# POWER.net
KiCad netlist of a schematic drawn in Altium Designer
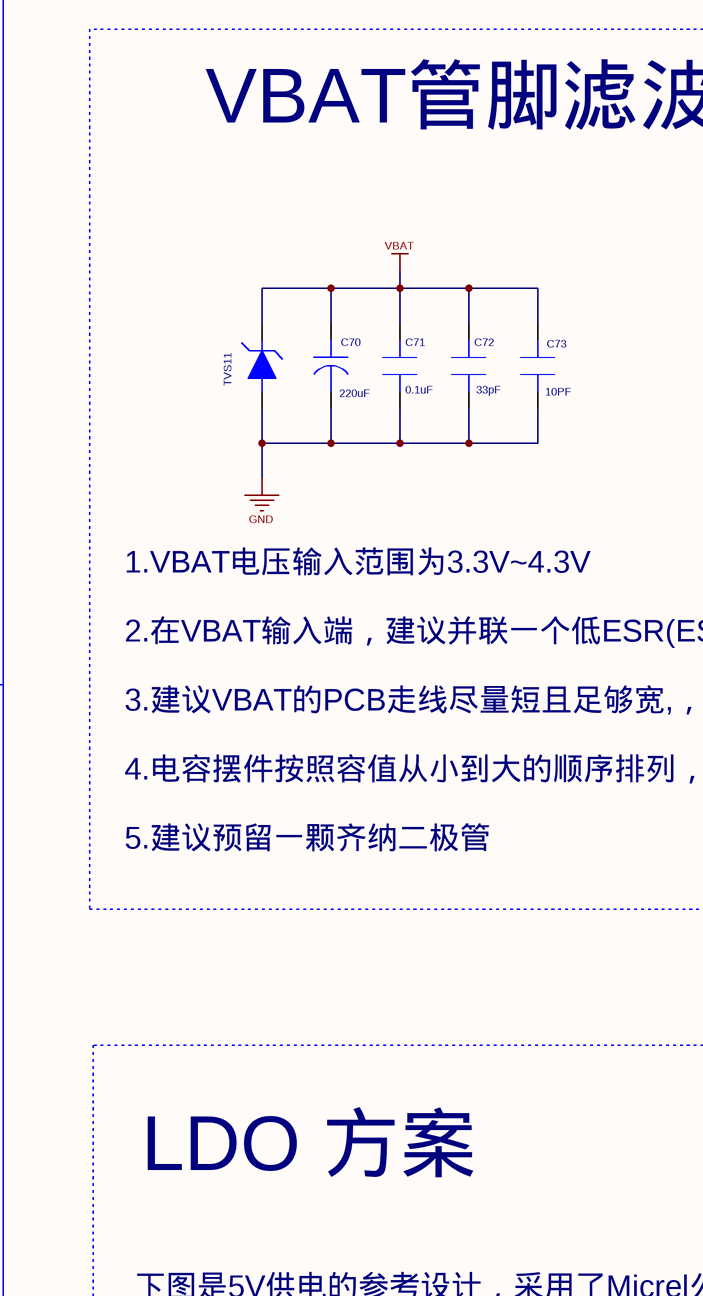
[diagram p0: POWER.SchDoc, top left]
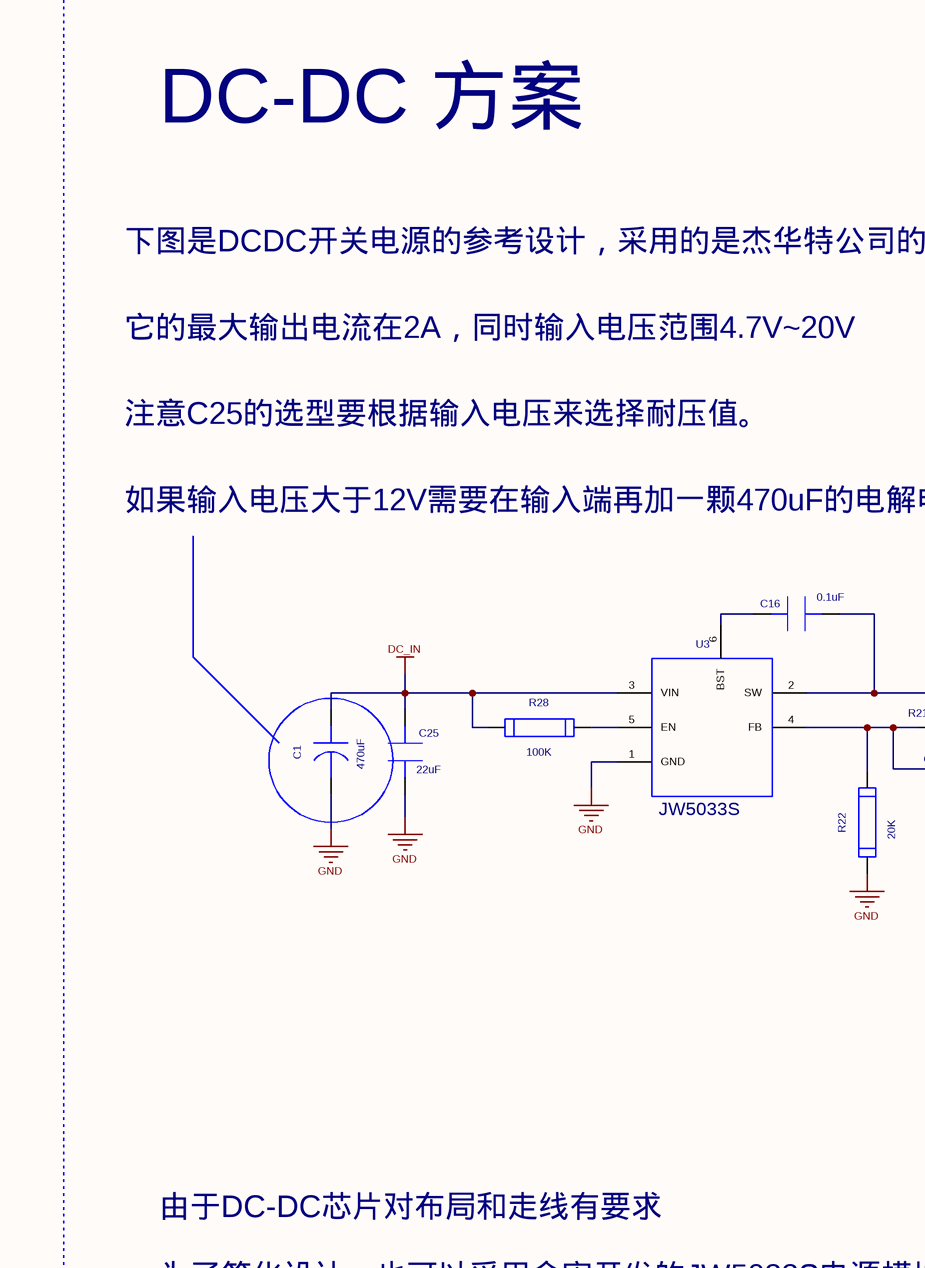
[diagram p1: POWER.SchDoc, top middle]
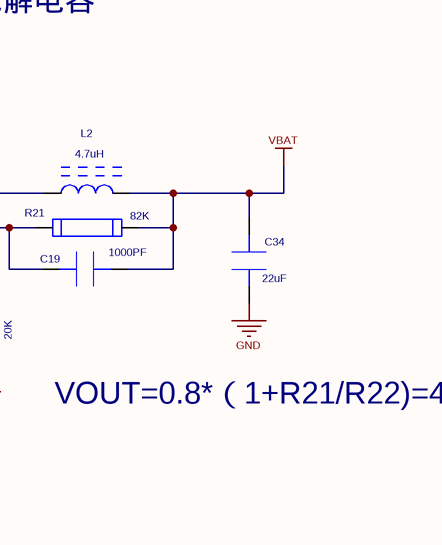
[diagram p2: POWER.SchDoc, top right]
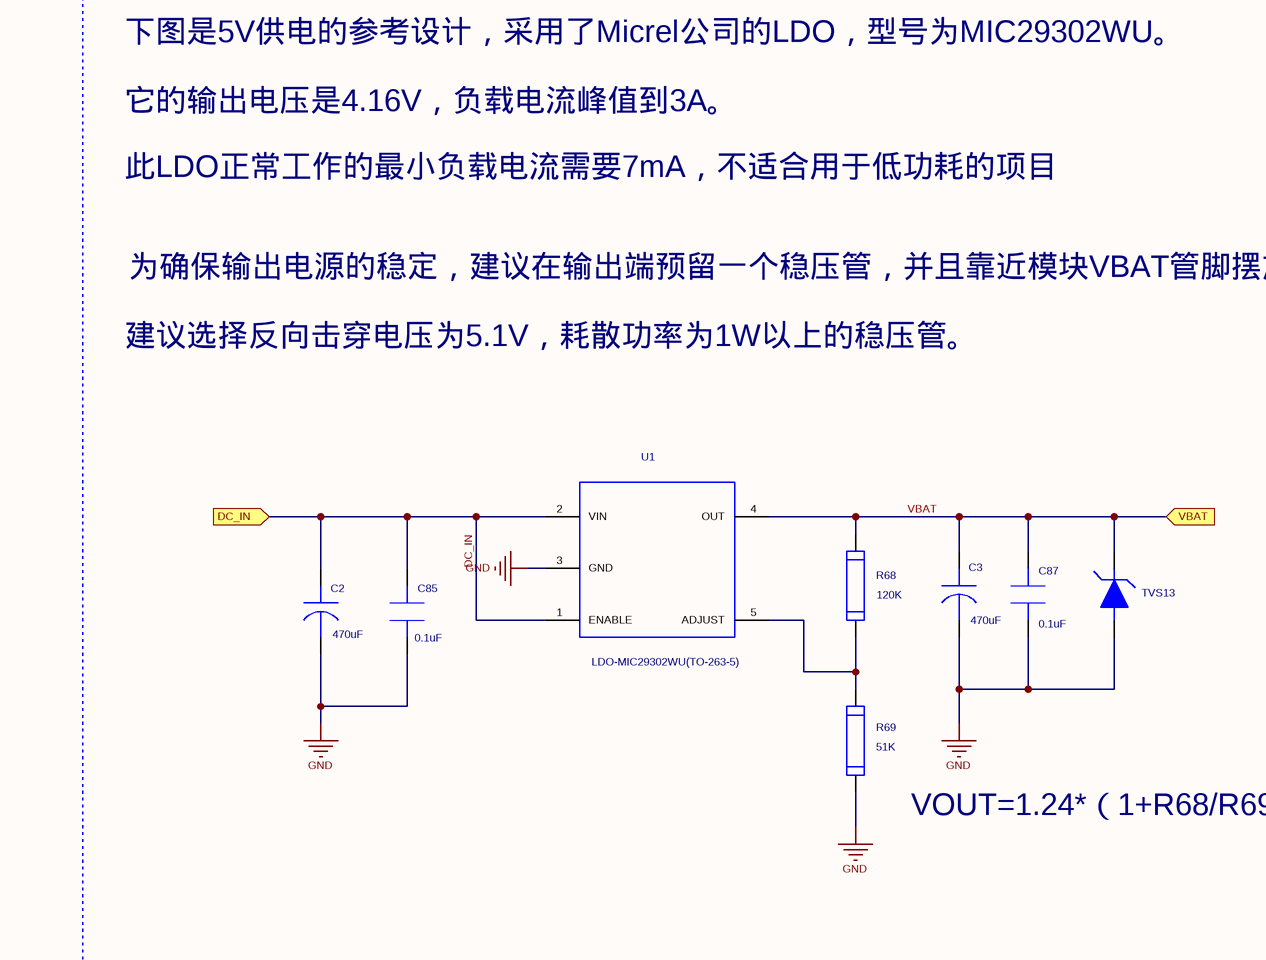
[diagram p3: POWER.SchDoc, bottom left]
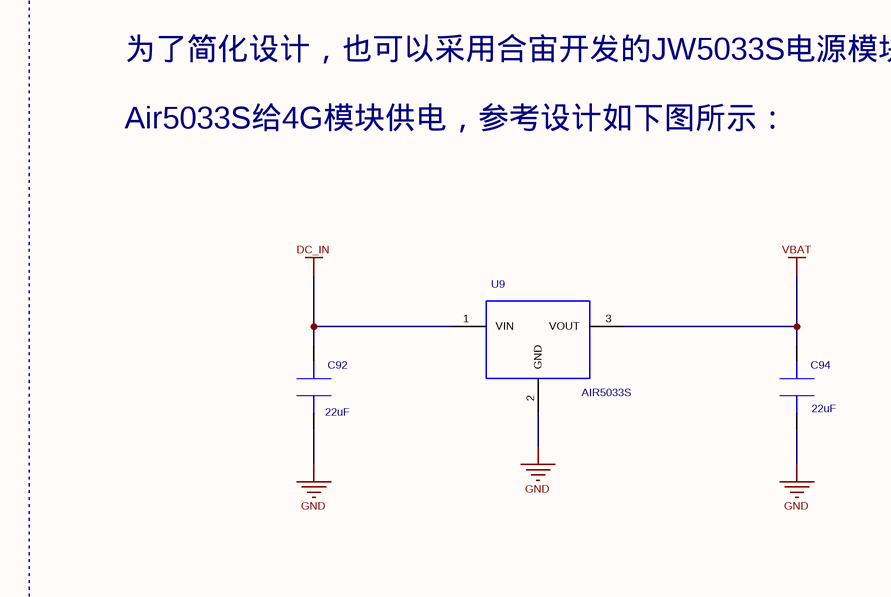
[diagram p4: POWER.SchDoc, bottom middle]
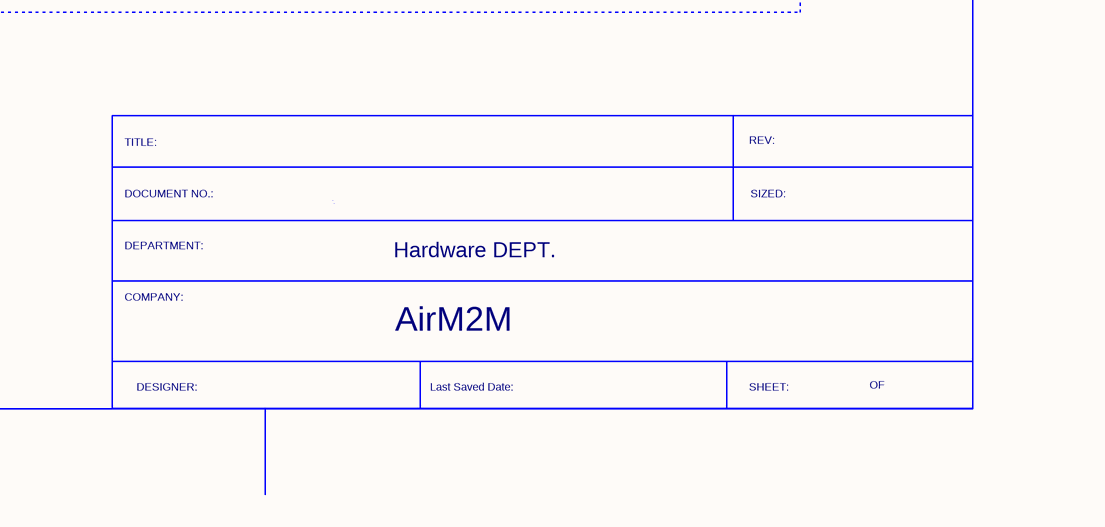
[diagram p5: POWER.SchDoc, bottom right]

(export (version "E")
  (design (tool "Eeschema 10.0.6"))
  (components
    (comp (ref "C1")
      (value "470uF")
      (footprint "CAP-PD-8MMX11.5MM-UVR1C471MPD")
      (description "铝电解电容器;470uF;+/-20%;16V;8x11.5mm;引脚间距3.5mm;ROHS")
      (fields (field (name "TOLERANCE") "+/-20%") (field (name "Comment") "CAP-AL-470UF-16V-8X11.5MM"))
      (libsource (lib "*") (part "CAP-AL-470UF-16V-8X11.5MM"))
    )
    (comp (ref "C2")
      (value "470uF")
      (footprint "CAP-PD-8MMX11.5MM-UVR1C471MPD")
      (description "铝电解电容器;470uF;+/-20%;16V;8x11.5mm;引脚间距3.5mm;ROHS")
      (fields (field (name "TOLERANCE") "+/-20%") (field (name "Comment") "CAP-AL-470UF-16V-8X11.5MM"))
      (libsource (lib "*") (part "CAP-AL-470UF-16V-8X11.5MM"))
    )
    (comp (ref "C3")
      (value "470uF")
      (footprint "CAP-PD-8MMX11.5MM-UVR1C471MPD")
      (description "铝电解电容器;470uF;+/-20%;16V;8x11.5mm;引脚间距3.5mm;ROHS")
      (fields (field (name "TOLERANCE") "+/-20%") (field (name "Comment") "CAP-AL-470UF-16V-8X11.5MM"))
      (libsource (lib "*") (part "CAP-AL-470UF-16V-8X11.5MM"))
    )
    (comp (ref "C16")
      (value "0.1uF")
      (footprint "SC0402")
      (description "CAP CER X5R/X7R;0.1uF;+/-10%;10V;0402;0.5mm;ROHS")
      (fields (field (name "TOLERANCE") "+/-10%") (field (name "Comment") "CAP-0.1UF-0402-X5R-10V"))
      (libsource (lib "*") (part "CAP-0.1UF-0402-X5R-10V"))
    )
    (comp (ref "C19")
      (value "1000PF")
      (footprint "SC0402")
      (description "CAP CER X7R;1000PF;+/-10%;50V;0402;0.5mm;ROHS")
      (fields (field (name "TOLERANCE") "+/-10%") (field (name "Comment") "CAP-1000PF-0402-X7R"))
      (libsource (lib "*") (part "CAP-1000PF-0402-X7R"))
    )
    (comp (ref "C25")
      (value "22uF")
      (footprint "SC0603")
      (description "CAP CER X5R;22uF;+/-20%;6.3V;0603;0.8mm;ROHS")
      (fields (field (name "TOLERANCE") "+/-20%") (field (name "Comment") "CAP-22UF-0603-X5R"))
      (libsource (lib "*") (part "CAP-22UF-0603-X5R"))
    )
    (comp (ref "C34")
      (value "22uF")
      (footprint "SC0603")
      (description "CAP CER X5R;4.7uF;+/-10%;6.3V;0603;0.8mm;ROHS")
      (fields (field (name "TOLERANCE") "+/-10%") (field (name "Comment") "CAP-4.7UF-0603-X5R"))
      (libsource (lib "*") (part "CAP-4.7UF-0603-X5R"))
    )
    (comp (ref "C70")
      (value "220uF")
      (footprint "CASEB")
      (description "CAP TAN;220uF;+/-20%;6.3V;CASEB;3.5*2.8*2.1mm;ROHS")
      (fields (field (name "TOLERANCE") "+/-20%") (field (name "Comment") "CAP-TAN-100UF-CASEB"))
      (libsource (lib "*") (part "CAP-TAN-100UF-CASEB"))
    )
    (comp (ref "C71")
      (value "0.1uF")
      (footprint "SC0402")
      (description "CAP CER X7R;0.1uF;+/-10%;16V;0402;0.5mm;ROHS")
      (fields (field (name "TOLERANCE") "+/-10%") (field (name "Comment") "CAP-0.1UF-0402-X7R"))
      (libsource (lib "*") (part "CAP-0.1UF-0402-X7R"))
    )
    (comp (ref "C72")
      (value "33pF")
      (footprint "SC0402")
      (description "CAP CER C0G;33PF;+/-5%;50V;0402;0.5mm;ROHS")
      (fields (field (name "TOLERANCE") "+/-5%") (field (name "Comment") "CAP-33PF-0402-C0G"))
      (libsource (lib "*") (part "CAP-33PF-0402-C0G"))
    )
    (comp (ref "C73")
      (value "10PF")
      (footprint "SC0402")
      (description "CAP CER C0G;10PF;+/-5%;50V;0402;0.5mm;ROHS")
      (fields (field (name "TOLERANCE") "+/-5%") (field (name "Comment") "CAP-10PF-0402-C0G"))
      (libsource (lib "*") (part "CAP-10PF-0402-C0G"))
    )
    (comp (ref "C85")
      (value "0.1uF")
      (footprint "SC0402")
      (description "CAP CER X7R;0.1uF;+/-10%;16V;0402;0.5mm;ROHS")
      (fields (field (name "TOLERANCE") "+/-10%") (field (name "Comment") "CAP-0.1UF-0402-X7R"))
      (libsource (lib "*") (part "CAP-0.1UF-0402-X7R"))
    )
    (comp (ref "C87")
      (value "0.1uF")
      (footprint "SC0402")
      (description "CAP CER X7R;0.1uF;+/-10%;16V;0402;0.5mm;ROHS")
      (fields (field (name "TOLERANCE") "+/-10%") (field (name "Comment") "CAP-0.1UF-0402-X7R"))
      (libsource (lib "*") (part "CAP-0.1UF-0402-X7R"))
    )
    (comp (ref "C92")
      (value "22uF")
      (footprint "SC0805")
      (description "CAP CER X5R;22uF;20%;6.3V;0805;1.25mm;ROHS")
      (fields (field (name "TOLERANCE") "20%") (field (name "Comment") "CAP-22UF-0805-X5R"))
      (libsource (lib "*") (part "CAP-22UF-0805-X5R"))
    )
    (comp (ref "C94")
      (value "22uF")
      (footprint "SC0805")
      (description "CAP CER X5R;22uF;20%;6.3V;0805;1.25mm;ROHS")
      (fields (field (name "TOLERANCE") "20%") (field (name "Comment") "CAP-22UF-0805-X5R"))
      (libsource (lib "*") (part "CAP-22UF-0805-X5R"))
    )
    (comp (ref "L2")
      (value "4.7uH")
      (footprint "MRSC252A12-4R7W-N")
      (fields (field (name "Comment") "MRSC252A12-4R7W-N"))
      (libsource (lib "*") (part "MRSC252A12-4R7W-N"))
    )
    (comp (ref "R21")
      (value "82K")
      (footprint "SR0402")
      (description "RES FILM;82K;+/-1%;1/16W;0402;0.4mm;ROHS")
      (fields (field (name "TOLERANCE") "+/-1%") (field (name "Comment") "RES-82K-+-1%-0402"))
      (libsource (lib "*") (part "RES-82K-+-1%-0402"))
    )
    (comp (ref "R22")
      (value "20K")
      (footprint "SR0402")
      (description "RES FILM;20K;+/-1%;1/16W;0402;0.4mm;ROHS")
      (fields (field (name "TOLERANCE") "+/-1%") (field (name "Comment") "RES-20K-+/-1%-0402"))
      (libsource (lib "*") (part "RES-20K-+/-1%-0402"))
    )
    (comp (ref "R28")
      (value "100K")
      (footprint "SR0402")
      (description "RES FILM;100K;+/-5%;1/16W;0402;0.4mm;ROHS")
      (fields (field (name "TOLERANCE") "+/-5%") (field (name "Comment") "RES-100K-0402"))
      (libsource (lib "*") (part "RES-100K-0402"))
    )
    (comp (ref "R68")
      (value "120K")
      (footprint "SR0402")
      (description "RES FILM;120K;+/-1%;1/16W;0402;0.4mm;ROHS")
      (fields (field (name "TOLERANCE") "1%") (field (name "Comment") "RES-120K-+-1%-0402"))
      (libsource (lib "*") (part "RES-120K-+-1%-0402"))
    )
    (comp (ref "R69")
      (value "51K")
      (footprint "SR0402")
      (description "RES FILM;51K;+/-5%;1/16W;0402;0.4mm;ROHS")
      (fields (field (name "TOLERANCE") "+/-5%") (field (name "Comment") "RES-51K-0402"))
      (libsource (lib "*") (part "RES-51K-0402"))
    )
    (comp (ref "TVS11")
      (value "ESD-TVS-PESDU4581P1H")
      (footprint "DFN1006")
      (description "TVS；4.5V；双向；400W；DFN1006-2;1*0.6*0.5mm;ROHS")
      (libsource (lib "*") (part "ESD-TVS-PESDU4581P1H"))
    )
    (comp (ref "TVS13")
      (value "ESD-TVS-PESDU4581P1H")
      (footprint "DFN1006")
      (description "TVS；4.5V；双向；400W；DFN1006-2;1*0.6*0.5mm;ROHS")
      (libsource (lib "*") (part "ESD-TVS-PESDU4581P1H"))
    )
    (comp (ref "U1")
      (value "LDO-MIC29302WU(TO-263-5)")
      (footprint "TO-263-5L")
      (description "LDO;Adjustable;3A;TO-263-5;4.5mm;ROHS")
      (fields (field (name "MANUFACTURER") "Micrel;"))
      (libsource (lib "*") (part "LDO-MIC29302WU(TO-263-5)"))
    )
    (comp (ref "U3") (value "JW5033H") (footprint "JW5033S") (libsource (lib "*") (part "JW5033H")))
    (comp (ref "U9") (value "AIR5033S") (footprint "A5033S") (libsource (lib "*") (part "AIR5033S")))
  )
  (nets
    (net (code "1") (name "DC_IN") (class "Default")
      (node (ref "C1") (pin "1") (pinfunction "1_1") (pintype "passive"))
      (node (ref "C2") (pin "1") (pinfunction "1_1") (pintype "passive"))
      (node (ref "C25") (pin "2") (pinfunction "2_2") (pintype "passive"))
      (node (ref "C85") (pin "1") (pinfunction "1_1") (pintype "passive"))
      (node (ref "C92") (pin "2") (pinfunction "2_2") (pintype "passive"))
      (node (ref "R28") (pin "1") (pinfunction "1_1") (pintype "passive"))
      (node (ref "U1") (pin "1") (pinfunction "ENABLE_1") (pintype "passive"))
      (node (ref "U1") (pin "2") (pinfunction "VIN_2") (pintype "passive"))
      (node (ref "U3") (pin "3") (pinfunction "VIN_3") (pintype "passive"))
      (node (ref "U9") (pin "1") (pinfunction "VIN_1") (pintype "power_in"))
    )
    (net (code "2") (name "GND") (class "Default")
      (node (ref "C1") (pin "2") (pinfunction "2_2") (pintype "passive"))
      (node (ref "C2") (pin "2") (pinfunction "2_2") (pintype "passive"))
      (node (ref "C25") (pin "1") (pinfunction "1_1") (pintype "passive"))
      (node (ref "C3") (pin "2") (pinfunction "2_2") (pintype "passive"))
      (node (ref "C34") (pin "1") (pinfunction "1_1") (pintype "passive"))
      (node (ref "C70") (pin "2") (pinfunction "2_2") (pintype "passive"))
      (node (ref "C71") (pin "2") (pinfunction "2_2") (pintype "passive"))
      (node (ref "C72") (pin "2") (pinfunction "2_2") (pintype "passive"))
      (node (ref "C73") (pin "2") (pinfunction "2_2") (pintype "passive"))
      (node (ref "C85") (pin "2") (pinfunction "2_2") (pintype "passive"))
      (node (ref "C87") (pin "2") (pinfunction "2_2") (pintype "passive"))
      (node (ref "C92") (pin "1") (pinfunction "1_1") (pintype "passive"))
      (node (ref "C94") (pin "1") (pinfunction "1_1") (pintype "passive"))
      (node (ref "R22") (pin "1") (pinfunction "1_1") (pintype "passive"))
      (node (ref "R69") (pin "1") (pinfunction "1_1") (pintype "passive"))
      (node (ref "TVS11") (pin "2") (pinfunction "2_2") (pintype "passive"))
      (node (ref "TVS13") (pin "2") (pinfunction "2_2") (pintype "passive"))
      (node (ref "U1") (pin "3") (pinfunction "GND_3") (pintype "passive"))
      (node (ref "U1") (pin "6") (pinfunction "GND_6") (pintype "power_in"))
      (node (ref "U3") (pin "1") (pinfunction "GND_1") (pintype "passive"))
      (node (ref "U9") (pin "2") (pinfunction "GND_2") (pintype "passive"))
    )
    (net (code "3") (name "Net-(U1-ADJUST)") (class "Default")
      (node (ref "R68") (pin "1") (pinfunction "1_1") (pintype "passive"))
      (node (ref "R69") (pin "2") (pinfunction "2_2") (pintype "passive"))
      (node (ref "U1") (pin "5") (pinfunction "ADJUST_5") (pintype "passive"))
    )
    (net (code "4") (name "Net-(U3-BST)") (class "Default")
      (node (ref "C16") (pin "1") (pinfunction "1_1") (pintype "passive"))
      (node (ref "U3") (pin "6") (pinfunction "BST_6") (pintype "passive"))
    )
    (net (code "5") (name "Net-(U3-EN)") (class "Default")
      (node (ref "R28") (pin "2") (pinfunction "2_2") (pintype "passive"))
      (node (ref "U3") (pin "5") (pinfunction "EN_5") (pintype "passive"))
    )
    (net (code "6") (name "Net-(U3-FB)") (class "Default")
      (node (ref "C19") (pin "1") (pinfunction "1_1") (pintype "passive"))
      (node (ref "R21") (pin "1") (pinfunction "1_1") (pintype "passive"))
      (node (ref "R22") (pin "2") (pinfunction "2_2") (pintype "passive"))
      (node (ref "U3") (pin "4") (pinfunction "FB_4") (pintype "passive"))
    )
    (net (code "7") (name "Net-(U3-SW)") (class "Default")
      (node (ref "C16") (pin "2") (pinfunction "2_2") (pintype "passive"))
      (node (ref "L2") (pin "1") (pinfunction "1_1") (pintype "passive"))
      (node (ref "U3") (pin "2") (pinfunction "SW_2") (pintype "passive"))
    )
    (net (code "8") (name "VBAT") (class "Default")
      (node (ref "C19") (pin "2") (pinfunction "2_2") (pintype "passive"))
      (node (ref "C3") (pin "1") (pinfunction "1_1") (pintype "passive"))
      (node (ref "C34") (pin "2") (pinfunction "2_2") (pintype "passive"))
      (node (ref "C70") (pin "1") (pinfunction "1_1") (pintype "passive"))
      (node (ref "C71") (pin "1") (pinfunction "1_1") (pintype "passive"))
      (node (ref "C72") (pin "1") (pinfunction "1_1") (pintype "passive"))
      (node (ref "C73") (pin "1") (pinfunction "1_1") (pintype "passive"))
      (node (ref "C87") (pin "1") (pinfunction "1_1") (pintype "passive"))
      (node (ref "C94") (pin "2") (pinfunction "2_2") (pintype "passive"))
      (node (ref "L2") (pin "2") (pinfunction "2_2") (pintype "passive"))
      (node (ref "R21") (pin "2") (pinfunction "2_2") (pintype "passive"))
      (node (ref "R68") (pin "2") (pinfunction "2_2") (pintype "passive"))
      (node (ref "TVS11") (pin "1") (pinfunction "1_1") (pintype "passive"))
      (node (ref "TVS13") (pin "1") (pinfunction "1_1") (pintype "passive"))
      (node (ref "U1") (pin "4") (pinfunction "OUT_4") (pintype "passive"))
      (node (ref "U9") (pin "3") (pinfunction "VOUT_3") (pintype "passive"))
    )
  )
)
